# pca20020_sheet5_motion_sensors.net
KiCad netlist of a schematic drawn in Altium Designer
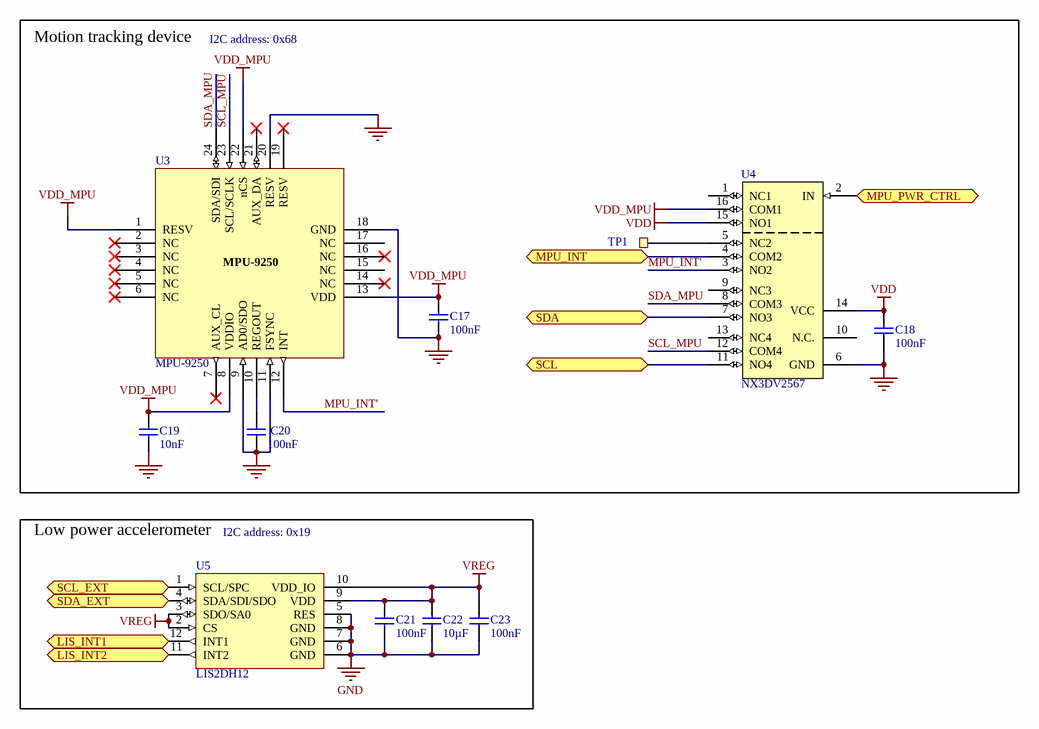
[diagram p0: pca20020_sheet5_motion_sensors.SchDoc]

(export (version "E")
  (design (tool "Eeschema 10.0.6"))
  (components
    (comp (ref "C17")
      (value "100nF")
      (footprint "CAPC1005X04L")
      (description "Capacitor, X7R, ±10%")
      (fields (field (name "PART NUMBER") "C0402-100n") (field (name "PUBLISHER") "Nordic Semiconductor"))
      (libsource (lib "Nordic Passive DB") (part "CAP"))
    )
    (comp (ref "C18")
      (value "100nF")
      (footprint "CAPC1005X04L")
      (description "Capacitor, X7R, ±10%")
      (fields (field (name "PART NUMBER") "C0402-100n") (field (name "PUBLISHER") "Nordic Semiconductor"))
      (libsource (lib "Nordic Passive DB") (part "CAP"))
    )
    (comp (ref "C19")
      (value "10nF")
      (footprint "CAPC1005X04L")
      (description "Capacitor, X7R, ±10%")
      (fields (field (name "PART NUMBER") "C0402-10n") (field (name "PUBLISHER") "Nordic Semiconductor"))
      (libsource (lib "Nordic Passive DB") (part "CAP"))
    )
    (comp (ref "C20")
      (value "100nF")
      (footprint "CAPC1005X04L")
      (description "Capacitor, X7R, ±10%")
      (fields (field (name "PART NUMBER") "C0402-100n") (field (name "PUBLISHER") "Nordic Semiconductor"))
      (libsource (lib "Nordic Passive DB") (part "CAP"))
    )
    (comp (ref "C21")
      (value "100nF")
      (footprint "CAPC1005X04L")
      (description "Capacitor, X7R, ±10%")
      (fields (field (name "PART NUMBER") "C0402-100n") (field (name "PUBLISHER") "Nordic Semiconductor"))
      (libsource (lib "Nordic Passive DB") (part "CAP"))
    )
    (comp (ref "C22")
      (value "10µF")
      (footprint "CAPC1608X06L")
      (description "Capacitor, X5R, ±20%")
      (fields (field (name "PART NUMBER") "C0603-10µ") (field (name "PUBLISHER") "Nordic Semiconductor"))
      (libsource (lib "Nordic Passive DB") (part "CAP"))
    )
    (comp (ref "C23")
      (value "100nF")
      (footprint "CAPC1005X04L")
      (description "Capacitor, X7R, ±10%")
      (fields (field (name "PART NUMBER") "C0402-100n") (field (name "PUBLISHER") "Nordic Semiconductor"))
      (libsource (lib "Nordic Passive DB") (part "CAP"))
    )
    (comp (ref "TP1")
      (value "TP")
      (footprint "TESTPAD-TH")
      (description "Testpoint, through hole")
      (fields (field (name "PART NUMBER") "Testpoint TH") (field (name "PUBLISHER") "Nordic Semiconductor"))
      (libsource (lib "Nordic Passive DB") (part "TESTPAD"))
    )
    (comp (ref "U3")
      (value "MPU-9250")
      (footprint "QFN40P300X300X105_HS-25N")
      (description "9-axis MotionTracking™ Device")
      (fields (field (name "MANUFACTURER") "InvenSense") (field (name "PUBLISHER") "Nordic Semiconductor"))
      (libsource (lib "Nordic Active DB") (part "MPU-9250"))
    )
    (comp (ref "U4")
      (value "NX3DV2567")
      (footprint "XQFN40P180X260X50-16N")
      (description "Low-ohmic four-pole double-throw analog switch")
      (fields
        (field (name "PART NUMBER") "NX3DV2567GU")
        (field (name "MANUFACTURER") "NXP Semiconductors")
        (field (name "PUBLISHER") "Nordic Semiconductor")
      )
      (libsource (lib "Nordic Active DB") (part "NX3DV2567"))
    )
    (comp (ref "U5")
      (value "LIS2DH12")
      (footprint "LGA50P200X200X100-12N")
      (description "3-axis - ±2g/±4g/±8g/±16g digital output femto accelerometer")
      (fields
        (field (name "MANUFACTURER") "STMicroelectronics")
        (field (name "2ND SOURCE PART NUMBER") "243-3081")
        (field (name "PUBLISHER") "Nordic Semiconductor")
      )
      (libsource (lib "Nordic Active DB") (part "LIS2xx12"))
    )
  )
  (nets
    (net (code "1") (name "/LIS_INT1") (class "Default")
      (node (ref "U5") (pin "12") (pinfunction "INT1_12") (pintype "output"))
    )
    (net (code "2") (name "/LIS_INT2") (class "Default")
      (node (ref "U5") (pin "11") (pinfunction "INT2_11") (pintype "output"))
    )
    (net (code "3") (name "/MPU_INT") (class "Default")
      (node (ref "U4") (pin "4") (pinfunction "COM2_4") (pintype "bidirectional"))
    )
    (net (code "4") (name "/MPU_INT'") (class "Default")
      (node (ref "U3") (pin "12") (pinfunction "INT_12") (pintype "output"))
      (node (ref "U4") (pin "3") (pinfunction "NO2_3") (pintype "bidirectional"))
    )
    (net (code "5") (name "/MPU_PWR_CTRL") (class "Default")
      (node (ref "U4") (pin "2") (pinfunction "IN_2") (pintype "input"))
    )
    (net (code "6") (name "/SCL") (class "Default")
      (node (ref "U4") (pin "11") (pinfunction "NO4_11") (pintype "bidirectional"))
    )
    (net (code "7") (name "/SCL_EXT") (class "Default")
      (node (ref "U5") (pin "1") (pinfunction "SCL/SPC_1") (pintype "input"))
    )
    (net (code "8") (name "/SCL_MPU") (class "Default")
      (node (ref "U3") (pin "23") (pinfunction "SCL/SCLK_23") (pintype "input"))
      (node (ref "U4") (pin "12") (pinfunction "COM4_12") (pintype "bidirectional"))
    )
    (net (code "9") (name "/SDA") (class "Default")
      (node (ref "U4") (pin "7") (pinfunction "NO3_7") (pintype "bidirectional"))
    )
    (net (code "10") (name "/SDA_EXT") (class "Default")
      (node (ref "U5") (pin "4") (pinfunction "SDA/SDI/SDO_4") (pintype "bidirectional"))
    )
    (net (code "11") (name "/SDA_MPU") (class "Default")
      (node (ref "U3") (pin "24") (pinfunction "SDA/SDI_24") (pintype "bidirectional"))
      (node (ref "U4") (pin "8") (pinfunction "COM3_8") (pintype "bidirectional"))
    )
    (net (code "12") (name "GND") (class "Default")
      (node (ref "C17") (pin "1") (pinfunction "1_1") (pintype "passive"))
      (node (ref "C18") (pin "1") (pinfunction "1_1") (pintype "passive"))
      (node (ref "C19") (pin "1") (pinfunction "1_1") (pintype "passive"))
      (node (ref "C20") (pin "1") (pinfunction "1_1") (pintype "passive"))
      (node (ref "C21") (pin "1") (pinfunction "1_1") (pintype "passive"))
      (node (ref "C22") (pin "1") (pinfunction "1_1") (pintype "passive"))
      (node (ref "C23") (pin "1") (pinfunction "1_1") (pintype "passive"))
      (node (ref "U3") (pin "11") (pinfunction "FSYNC_11") (pintype "input"))
      (node (ref "U3") (pin "18") (pinfunction "GND_18") (pintype "power_in"))
      (node (ref "U3") (pin "20") (pinfunction "RESV_20") (pintype "passive"))
      (node (ref "U3") (pin "9") (pinfunction "AD0/SDO_9") (pintype "input"))
      (node (ref "U4") (pin "6") (pinfunction "GND_6") (pintype "power_in"))
      (node (ref "U5") (pin "5") (pinfunction "RES_5") (pintype "passive"))
      (node (ref "U5") (pin "6") (pinfunction "GND_6") (pintype "power_in"))
      (node (ref "U5") (pin "7") (pinfunction "GND_7") (pintype "power_in"))
      (node (ref "U5") (pin "8") (pinfunction "GND_8") (pintype "power_in"))
    )
    (net (code "13") (name "Net-(U3-REGOUT)") (class "Default")
      (node (ref "C20") (pin "2") (pinfunction "2_2") (pintype "passive"))
      (node (ref "U3") (pin "10") (pinfunction "REGOUT_10") (pintype "passive"))
    )
    (net (code "14") (name "Net-(U4-NC2)") (class "Default")
      (node (ref "TP1") (pin "1") (pinfunction "1_1") (pintype "passive"))
      (node (ref "U4") (pin "5") (pinfunction "NC2_5") (pintype "bidirectional"))
    )
    (net (code "15") (name "VDD") (class "Default")
      (node (ref "C18") (pin "2") (pinfunction "2_2") (pintype "passive"))
      (node (ref "U4") (pin "14") (pinfunction "VCC_14") (pintype "power_in"))
      (node (ref "U4") (pin "15") (pinfunction "NO1_15") (pintype "bidirectional"))
    )
    (net (code "16") (name "VDD_MPU") (class "Default")
      (node (ref "C17") (pin "2") (pinfunction "2_2") (pintype "passive"))
      (node (ref "C19") (pin "2") (pinfunction "2_2") (pintype "passive"))
      (node (ref "U3") (pin "1") (pinfunction "RESV_1") (pintype "passive"))
      (node (ref "U3") (pin "13") (pinfunction "VDD_13") (pintype "power_in"))
      (node (ref "U3") (pin "22") (pinfunction "nCS_22") (pintype "input"))
      (node (ref "U3") (pin "8") (pinfunction "VDDIO_8") (pintype "power_in"))
      (node (ref "U4") (pin "16") (pinfunction "COM1_16") (pintype "bidirectional"))
    )
    (net (code "17") (name "VREG") (class "Default")
      (node (ref "C21") (pin "2") (pinfunction "2_2") (pintype "passive"))
      (node (ref "C22") (pin "2") (pinfunction "2_2") (pintype "passive"))
      (node (ref "C23") (pin "2") (pinfunction "2_2") (pintype "passive"))
      (node (ref "U5") (pin "10") (pinfunction "VDD_IO_10") (pintype "power_in"))
      (node (ref "U5") (pin "2") (pinfunction "CS_2") (pintype "input"))
      (node (ref "U5") (pin "3") (pinfunction "SDO/SA0_3") (pintype "bidirectional"))
      (node (ref "U5") (pin "9") (pinfunction "VDD_9") (pintype "power_in"))
    )
    (net (code "18") (name "unconnected-(U3-AUX_CL-Pad7)") (class "Default")
      (node (ref "U3") (pin "7") (pinfunction "AUX_CL_7") (pintype "output+no_connect"))
    )
    (net (code "19") (name "unconnected-(U3-AUX_DA-Pad21)") (class "Default")
      (node (ref "U3") (pin "21") (pinfunction "AUX_DA_21") (pintype "bidirectional+no_connect"))
    )
    (net (code "20") (name "unconnected-(U3-NC-Pad2)") (class "Default")
      (node (ref "U3") (pin "2") (pinfunction "NC_2") (pintype "passive+no_connect"))
    )
    (net (code "21") (name "unconnected-(U3-NC-Pad3)") (class "Default")
      (node (ref "U3") (pin "3") (pinfunction "NC_3") (pintype "passive+no_connect"))
    )
    (net (code "22") (name "unconnected-(U3-NC-Pad4)") (class "Default")
      (node (ref "U3") (pin "4") (pinfunction "NC_4") (pintype "passive+no_connect"))
    )
    (net (code "23") (name "unconnected-(U3-NC-Pad5)") (class "Default")
      (node (ref "U3") (pin "5") (pinfunction "NC_5") (pintype "passive+no_connect"))
    )
    (net (code "24") (name "unconnected-(U3-NC-Pad6)") (class "Default")
      (node (ref "U3") (pin "6") (pinfunction "NC_6") (pintype "passive+no_connect"))
    )
    (net (code "25") (name "unconnected-(U3-NC-Pad14)") (class "Default")
      (node (ref "U3") (pin "14") (pinfunction "NC_14") (pintype "passive+no_connect"))
    )
    (net (code "26") (name "unconnected-(U3-NC-Pad15)") (class "Default")
      (node (ref "U3") (pin "15") (pinfunction "NC_15") (pintype "passive"))
    )
    (net (code "27") (name "unconnected-(U3-NC-Pad16)") (class "Default")
      (node (ref "U3") (pin "16") (pinfunction "NC_16") (pintype "passive+no_connect"))
    )
    (net (code "28") (name "unconnected-(U3-NC-Pad17)") (class "Default")
      (node (ref "U3") (pin "17") (pinfunction "NC_17") (pintype "passive"))
    )
    (net (code "29") (name "unconnected-(U3-RESV-Pad19)") (class "Default")
      (node (ref "U3") (pin "19") (pinfunction "RESV_19") (pintype "passive+no_connect"))
    )
    (net (code "30") (name "unconnected-(U4-N.C.-Pad10)") (class "Default")
      (node (ref "U4") (pin "10") (pinfunction "N.C._10") (pintype "passive"))
    )
    (net (code "31") (name "unconnected-(U4-NC1-Pad1)") (class "Default")
      (node (ref "U4") (pin "1") (pinfunction "NC1_1") (pintype "bidirectional"))
    )
    (net (code "32") (name "unconnected-(U4-NC3-Pad9)") (class "Default")
      (node (ref "U4") (pin "9") (pinfunction "NC3_9") (pintype "bidirectional"))
    )
    (net (code "33") (name "unconnected-(U4-NC4-Pad13)") (class "Default")
      (node (ref "U4") (pin "13") (pinfunction "NC4_13") (pintype "bidirectional"))
    )
  )
)
